# Sheet1.net
KiCad netlist of a schematic drawn in Altium Designer
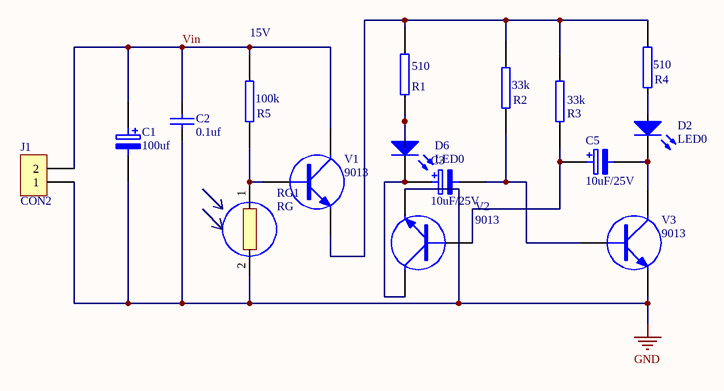
[diagram p0: Sheet1.SchDoc]

(export (version "E")
  (design (tool "Eeschema 10.0.6"))
  (components
    (comp (ref "C1")
      (value "100uf")
      (footprint "RB5/8")
      (description "Electrolytic Capacitor")
      (libsource (lib "lm317led") (part "ELECTRO2"))
    )
    (comp (ref "C2")
      (value "0.1uf")
      (footprint "RAD4")
      (description "Capacitor")
      (libsource (lib "lm317led") (part "CAP"))
    )
    (comp (ref "C3")
      (value "10uF/25V")
      (footprint "RB4/5")
      (description "Electrolytic Capacitor")
      (libsource (lib "lm317led") (part "ELECTRO2_1"))
    )
    (comp (ref "C5")
      (value "10uF/25V")
      (footprint "RB4/5")
      (description "Electrolytic Capacitor")
      (libsource (lib "lm317led") (part "ELECTRO2_1"))
    )
    (comp (ref "D2")
      (value "LED0")
      (footprint "LED-0")
      (description "Typical INFRARED GaAs LED")
      (fields (field (name "PUBLISHER") "Altium Limited"))
      (libsource (lib "lm317led") (part "LED0"))
    )
    (comp (ref "D6")
      (value "LED0")
      (footprint "LED-0")
      (description "Typical INFRARED GaAs LED")
      (fields (field (name "PUBLISHER") "Altium Limited"))
      (libsource (lib "lm317led") (part "LED0"))
    )
    (comp (ref "J1")
      (value "CON2")
      (footprint "HDR1X2")
      (description "Connector")
      (libsource (lib "lm317led") (part "CON2_5"))
    )
    (comp (ref "R1") (value "510") (footprint "AXIAL0.4") (libsource (lib "lm317led") (part "RES2")))
    (comp (ref "R2") (value "33k") (footprint "AXIAL0.4") (libsource (lib "lm317led") (part "RES2")))
    (comp (ref "R3") (value "33k") (footprint "AXIAL0.4") (libsource (lib "lm317led") (part "RES2")))
    (comp (ref "R4") (value "510") (footprint "AXIAL0.4") (libsource (lib "lm317led") (part "RES2")))
    (comp (ref "R5") (value "100k") (footprint "AXIAL0.4") (libsource (lib "lm317led") (part "RES2")))
    (comp (ref "RG1") (value "RG") (footprint "RB5/8-D") (libsource (lib "light") (part "RG")))
    (comp (ref "V1")
      (value "9013")
      (footprint "T3-111")
      (description "NPN Transistor")
      (libsource (lib "light") (part "NPN_111"))
    )
    (comp (ref "V2")
      (value "9013")
      (footprint "T3-111")
      (description "NPN Transistor")
      (libsource (lib "light") (part "NPN_111"))
    )
    (comp (ref "V3")
      (value "9013")
      (footprint "T3-111")
      (description "NPN Transistor")
      (libsource (lib "light") (part "NPN_111"))
    )
  )
  (nets
    (net (code "1") (name "/Vin") (class "Default")
      (node (ref "C1") (pin "1") (pinfunction "1_1") (pintype "passive"))
      (node (ref "C2") (pin "1") (pinfunction "1_1") (pintype "passive"))
      (node (ref "J1") (pin "2") (pinfunction "2_2") (pintype "passive"))
      (node (ref "R5") (pin "2") (pinfunction "2_2") (pintype "passive"))
      (node (ref "V1") (pin "3") (pinfunction "C_3") (pintype "passive"))
    )
    (net (code "2") (name "GND") (class "Default")
      (node (ref "C1") (pin "2") (pinfunction "2_2") (pintype "passive"))
      (node (ref "C2") (pin "2") (pinfunction "2_2") (pintype "passive"))
      (node (ref "J1") (pin "1") (pinfunction "1_1") (pintype "passive"))
      (node (ref "RG1") (pin "2") (pinfunction "2_2") (pintype "passive"))
      (node (ref "V2") (pin "1") (pinfunction "E_1") (pintype "passive"))
      (node (ref "V3") (pin "1") (pinfunction "E_1") (pintype "passive"))
    )
    (net (code "3") (name "Net-(D2-A)") (class "Default")
      (node (ref "D2") (pin "1") (pinfunction "A_1") (pintype "passive"))
      (node (ref "R4") (pin "1") (pinfunction "1_1") (pintype "passive"))
    )
    (net (code "4") (name "Net-(D2-K)") (class "Default")
      (node (ref "C5") (pin "2") (pinfunction "2_2") (pintype "passive"))
      (node (ref "D2") (pin "2") (pinfunction "K_2") (pintype "passive"))
      (node (ref "V3") (pin "3") (pinfunction "C_3") (pintype "passive"))
    )
    (net (code "5") (name "Net-(D6-A)") (class "Default")
      (node (ref "D6") (pin "1") (pinfunction "A_1") (pintype "passive"))
      (node (ref "R1") (pin "1") (pinfunction "1_1") (pintype "passive"))
    )
    (net (code "6") (name "Net-(D6-K)") (class "Default")
      (node (ref "C3") (pin "1") (pinfunction "1_1") (pintype "passive"))
      (node (ref "D6") (pin "2") (pinfunction "K_2") (pintype "passive"))
      (node (ref "V2") (pin "3") (pinfunction "C_3") (pintype "passive"))
    )
    (net (code "7") (name "Net-(V1-B)") (class "Default")
      (node (ref "R5") (pin "1") (pinfunction "1_1") (pintype "passive"))
      (node (ref "RG1") (pin "1") (pinfunction "1_1") (pintype "passive"))
      (node (ref "V1") (pin "2") (pinfunction "B_2") (pintype "passive"))
    )
    (net (code "8") (name "Net-(V1-E)") (class "Default")
      (node (ref "R1") (pin "2") (pinfunction "2_2") (pintype "passive"))
      (node (ref "R2") (pin "2") (pinfunction "2_2") (pintype "passive"))
      (node (ref "R3") (pin "2") (pinfunction "2_2") (pintype "passive"))
      (node (ref "R4") (pin "2") (pinfunction "2_2") (pintype "passive"))
      (node (ref "V1") (pin "1") (pinfunction "E_1") (pintype "passive"))
    )
    (net (code "9") (name "Net-(V2-B)") (class "Default")
      (node (ref "C5") (pin "1") (pinfunction "1_1") (pintype "passive"))
      (node (ref "R3") (pin "1") (pinfunction "1_1") (pintype "passive"))
      (node (ref "V2") (pin "2") (pinfunction "B_2") (pintype "passive"))
    )
    (net (code "10") (name "Net-(V3-B)") (class "Default")
      (node (ref "C3") (pin "2") (pinfunction "2_2") (pintype "passive"))
      (node (ref "R2") (pin "1") (pinfunction "1_1") (pintype "passive"))
      (node (ref "V3") (pin "2") (pinfunction "B_2") (pintype "passive"))
    )
  )
)
